# Thermocouple.net
KiCad netlist of a schematic drawn in Altium Designer
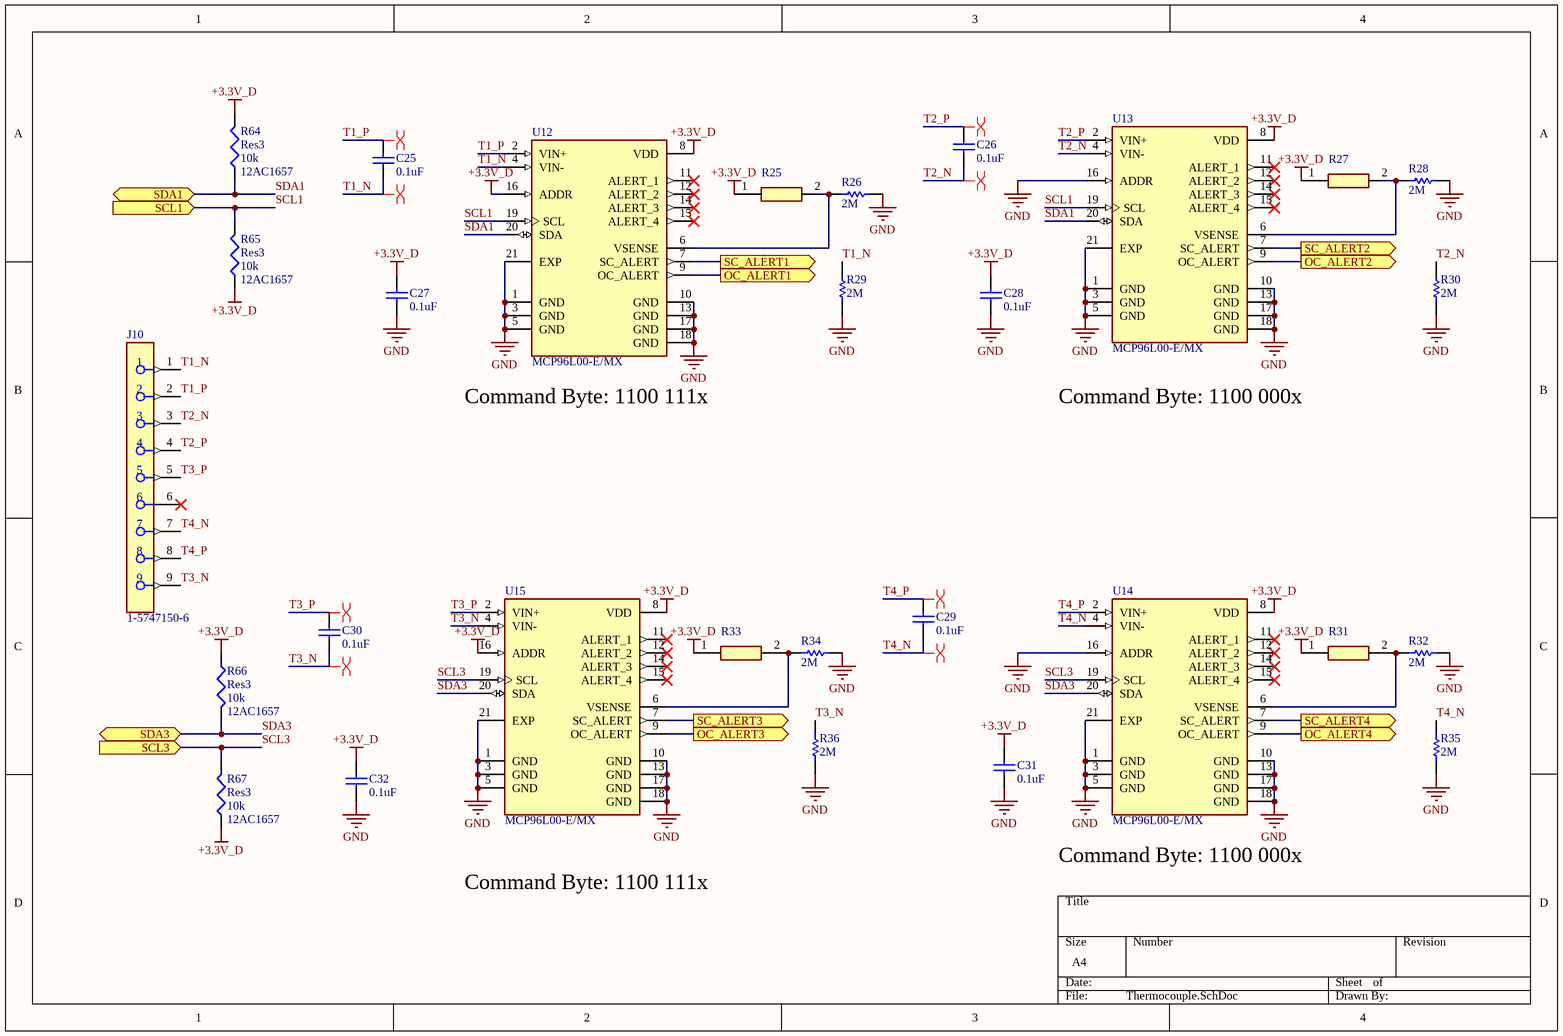
[diagram p0: Thermocouple.SchDoc]

(export (version "E")
  (design (tool "Eeschema 10.0.6"))
  (components
    (comp (ref "C25")
      (value "0.1uF")
      (footprint "CAPC1608X90X35NL15T15")
      (fields
        (field (name "PART NUMBER") "0603YC104JAT2A")
        (field (name "MANUFACTURER") "AVX Interconnect / Elco")
      )
      (libsource (lib "Altium Content Vault") (part "CAP"))
    )
    (comp (ref "C26")
      (value "0.1uF")
      (footprint "CAPC1608X90X35NL15T15")
      (fields
        (field (name "PART NUMBER") "0603YC104JAT2A")
        (field (name "MANUFACTURER") "AVX Interconnect / Elco")
      )
      (libsource (lib "Altium Content Vault") (part "CAP"))
    )
    (comp (ref "C27")
      (value "0.1uF")
      (footprint "CAPC1608X90X35NL15T15")
      (fields
        (field (name "PART NUMBER") "0603YC104JAT2A")
        (field (name "MANUFACTURER") "AVX Interconnect / Elco")
      )
      (libsource (lib "Altium Content Vault") (part "CAP"))
    )
    (comp (ref "C28")
      (value "0.1uF")
      (footprint "CAPC1608X90X35NL15T15")
      (fields
        (field (name "PART NUMBER") "0603YC104JAT2A")
        (field (name "MANUFACTURER") "AVX Interconnect / Elco")
      )
      (libsource (lib "Altium Content Vault") (part "CAP"))
    )
    (comp (ref "C29")
      (value "0.1uF")
      (footprint "CAPC1608X90X35NL15T15")
      (fields
        (field (name "PART NUMBER") "0603YC104JAT2A")
        (field (name "MANUFACTURER") "AVX Interconnect / Elco")
      )
      (libsource (lib "Altium Content Vault") (part "CAP"))
    )
    (comp (ref "C30")
      (value "0.1uF")
      (footprint "CAPC1608X90X35NL15T15")
      (fields
        (field (name "PART NUMBER") "0603YC104JAT2A")
        (field (name "MANUFACTURER") "AVX Interconnect / Elco")
      )
      (libsource (lib "Altium Content Vault") (part "CAP"))
    )
    (comp (ref "C31")
      (value "0.1uF")
      (footprint "CAPC1608X90X35NL15T15")
      (fields
        (field (name "PART NUMBER") "0603YC104JAT2A")
        (field (name "MANUFACTURER") "AVX Interconnect / Elco")
      )
      (libsource (lib "Altium Content Vault") (part "CAP"))
    )
    (comp (ref "C32")
      (value "0.1uF")
      (footprint "CAPC1608X90X35NL15T15")
      (fields
        (field (name "PART NUMBER") "0603YC104JAT2A")
        (field (name "MANUFACTURER") "AVX Interconnect / Elco")
      )
      (libsource (lib "Altium Content Vault") (part "CAP"))
    )
    (comp (ref "J10")
      (value "1-5747150-6")
      (footprint "FP-1-5747150-6-MFG")
      (description "CONN D-SUB RCPT 9POS VERT SOLDER")
      (fields
        (field (name "OCTOPART") "https://octopart.com/1-5747150-6-te+connectivity-39500344")
        (field (name "MANUFACTURER") "TE Connectivity")
      )
      (libsource (lib "Altium Content Vault") (part "deee9d0d87fff07c08bdfa5b86cd5a5"))
    )
    (comp (ref "R25")
      (value "ERJ-U02F1004X")
      (footprint "SamacSys:ERJS02_U02_(0402)")
      (description "Resistor")
      (libsource (lib "*") (part "ERJ-U02F1004X"))
    )
    (comp (ref "R26")
      (value "ERJ-2GEJ205X")
      (footprint "RESC1005X40X25LL05T05")
      (fields (field (name "MANUFACTURER") "Panasonic") (field (name "RESISTANCE") "2M"))
      (libsource (lib "Altium Content Vault") (part "RES"))
    )
    (comp (ref "R27")
      (value "ERJ-U02F1004X")
      (footprint "SamacSys:ERJS02_U02_(0402)")
      (description "Resistor")
      (libsource (lib "*") (part "ERJ-U02F1004X"))
    )
    (comp (ref "R28")
      (value "ERJ-2GEJ205X")
      (footprint "RESC1005X40X25LL05T05")
      (fields (field (name "MANUFACTURER") "Panasonic") (field (name "RESISTANCE") "2M"))
      (libsource (lib "Altium Content Vault") (part "RES"))
    )
    (comp (ref "R29")
      (value "ERJ-2GEJ205X")
      (footprint "RESC1005X40X25LL05T05")
      (fields (field (name "MANUFACTURER") "Panasonic") (field (name "RESISTANCE") "2M"))
      (libsource (lib "Altium Content Vault") (part "RES"))
    )
    (comp (ref "R30")
      (value "ERJ-2GEJ205X")
      (footprint "RESC1005X40X25LL05T05")
      (fields (field (name "MANUFACTURER") "Panasonic") (field (name "RESISTANCE") "2M"))
      (libsource (lib "Altium Content Vault") (part "RES"))
    )
    (comp (ref "R31")
      (value "ERJ-U02F1004X")
      (footprint "SamacSys:ERJS02_U02_(0402)")
      (description "Resistor")
      (libsource (lib "*") (part "ERJ-U02F1004X"))
    )
    (comp (ref "R32")
      (value "ERJ-2GEJ205X")
      (footprint "RESC1005X40X25LL05T05")
      (fields (field (name "MANUFACTURER") "Panasonic") (field (name "RESISTANCE") "2M"))
      (libsource (lib "Altium Content Vault") (part "RES"))
    )
    (comp (ref "R33")
      (value "ERJ-U02F1004X")
      (footprint "SamacSys:ERJS02_U02_(0402)")
      (description "Resistor")
      (libsource (lib "*") (part "ERJ-U02F1004X"))
    )
    (comp (ref "R34")
      (value "ERJ-2GEJ205X")
      (footprint "RESC1005X40X25LL05T05")
      (fields (field (name "MANUFACTURER") "Panasonic") (field (name "RESISTANCE") "2M"))
      (libsource (lib "Altium Content Vault") (part "RES"))
    )
    (comp (ref "R35")
      (value "ERJ-2GEJ205X")
      (footprint "RESC1005X40X25LL05T05")
      (fields (field (name "MANUFACTURER") "Panasonic") (field (name "RESISTANCE") "2M"))
      (libsource (lib "Altium Content Vault") (part "RES"))
    )
    (comp (ref "R36")
      (value "ERJ-2GEJ205X")
      (footprint "RESC1005X40X25LL05T05")
      (fields (field (name "MANUFACTURER") "Panasonic") (field (name "RESISTANCE") "2M"))
      (libsource (lib "Altium Content Vault") (part "RES"))
    )
    (comp (ref "R64")
      (value "Res3")
      (footprint "6-0805_L")
      (description "VISHAY BC COMPONENTS   MCT06030C1002FP500   RESISTOR, 0603, 10KOHM, 100mW, 1PER")
      (fields
        (field (name "ALTIUM_VALUE") "10k")
        (field (name "SUPPLIER PART NUMBER 1") "12AC1657")
        (field (name "MANUFACTURER") "Vishay")
        (field (name "MANUFACTURER PART NUMBER") "MCT06030C1002FP500")
        (field (name "PUBLISHER") "Altium Limited")
      )
      (libsource (lib "Miscellaneous Devices") (part "Res3"))
    )
    (comp (ref "R65")
      (value "Res3")
      (footprint "6-0805_L")
      (description "VISHAY BC COMPONENTS   MCT06030C1002FP500   RESISTOR, 0603, 10KOHM, 100mW, 1PER")
      (fields
        (field (name "ALTIUM_VALUE") "10k")
        (field (name "SUPPLIER PART NUMBER 1") "12AC1657")
        (field (name "MANUFACTURER") "Vishay")
        (field (name "MANUFACTURER PART NUMBER") "MCT06030C1002FP500")
        (field (name "PUBLISHER") "Altium Limited")
      )
      (libsource (lib "Miscellaneous Devices") (part "Res3"))
    )
    (comp (ref "R66")
      (value "Res3")
      (footprint "6-0805_L")
      (description "VISHAY BC COMPONENTS   MCT06030C1002FP500   RESISTOR, 0603, 10KOHM, 100mW, 1PER")
      (fields
        (field (name "ALTIUM_VALUE") "10k")
        (field (name "SUPPLIER PART NUMBER 1") "12AC1657")
        (field (name "MANUFACTURER") "Vishay")
        (field (name "MANUFACTURER PART NUMBER") "MCT06030C1002FP500")
        (field (name "PUBLISHER") "Altium Limited")
      )
      (libsource (lib "Miscellaneous Devices") (part "Res3"))
    )
    (comp (ref "R67")
      (value "Res3")
      (footprint "6-0805_L")
      (description "VISHAY BC COMPONENTS   MCT06030C1002FP500   RESISTOR, 0603, 10KOHM, 100mW, 1PER")
      (fields
        (field (name "ALTIUM_VALUE") "10k")
        (field (name "SUPPLIER PART NUMBER 1") "12AC1657")
        (field (name "MANUFACTURER") "Vishay")
        (field (name "MANUFACTURER PART NUMBER") "MCT06030C1002FP500")
        (field (name "PUBLISHER") "Altium Limited")
      )
      (libsource (lib "Miscellaneous Devices") (part "Res3"))
    )
    (comp (ref "U12")
      (value "MCP96L00-E/MX")
      (footprint "WB-AV-4510-DAQ:QFN65P500X500X100-21N_MCP9600-E/MX")
      (description "IC THERMOCOUPLE TO I2C 20MQFN")
      (fields (field (name "MF") "Microchip"))
      (libsource (lib "WB-AV-4510-DAQ") (part "MCP96001-E/MX"))
    )
    (comp (ref "U13")
      (value "MCP96L00-E/MX")
      (footprint "WB-AV-4510-DAQ:QFN65P500X500X100-21N_MCP9600-E/MX")
      (description "IC THERMOCOUPLE TO I2C 20MQFN")
      (fields (field (name "MF") "Microchip"))
      (libsource (lib "WB-AV-4510-DAQ") (part "MCP96001-E/MX"))
    )
    (comp (ref "U14")
      (value "MCP96L00-E/MX")
      (footprint "WB-AV-4510-DAQ:QFN65P500X500X100-21N_MCP9600-E/MX")
      (description "IC THERMOCOUPLE TO I2C 20MQFN")
      (fields (field (name "MF") "Microchip"))
      (libsource (lib "WB-AV-4510-DAQ") (part "MCP96001-E/MX"))
    )
    (comp (ref "U15")
      (value "MCP96L00-E/MX")
      (footprint "WB-AV-4510-DAQ:QFN65P500X500X100-21N_MCP9600-E/MX")
      (description "IC THERMOCOUPLE TO I2C 20MQFN")
      (fields (field (name "MF") "Microchip"))
      (libsource (lib "WB-AV-4510-DAQ") (part "MCP96001-E/MX"))
    )
  )
  (nets
    (net (code "1") (name "+3.3V_D") (class "Default")
      (node (ref "C27") (pin "2") (pinfunction "2_2") (pintype "passive"))
      (node (ref "C28") (pin "2") (pinfunction "2_2") (pintype "passive"))
      (node (ref "C31") (pin "2") (pinfunction "2_2") (pintype "passive"))
      (node (ref "C32") (pin "2") (pinfunction "2_2") (pintype "passive"))
      (node (ref "R25") (pin "1") (pinfunction "1_1") (pintype "passive"))
      (node (ref "R27") (pin "1") (pinfunction "1_1") (pintype "passive"))
      (node (ref "R31") (pin "1") (pinfunction "1_1") (pintype "passive"))
      (node (ref "R33") (pin "1") (pinfunction "1_1") (pintype "passive"))
      (node (ref "R64") (pin "2") (pinfunction "2_2") (pintype "passive"))
      (node (ref "R65") (pin "1") (pinfunction "1_1") (pintype "passive"))
      (node (ref "R66") (pin "1") (pinfunction "1_1") (pintype "passive"))
      (node (ref "R67") (pin "1") (pinfunction "1_1") (pintype "passive"))
      (node (ref "U12") (pin "16") (pinfunction "ADDR_16") (pintype "input"))
      (node (ref "U12") (pin "8") (pinfunction "VDD_8") (pintype "power_in"))
      (node (ref "U13") (pin "8") (pinfunction "VDD_8") (pintype "power_in"))
      (node (ref "U14") (pin "8") (pinfunction "VDD_8") (pintype "power_in"))
      (node (ref "U15") (pin "16") (pinfunction "ADDR_16") (pintype "input"))
      (node (ref "U15") (pin "8") (pinfunction "VDD_8") (pintype "power_in"))
    )
    (net (code "2") (name "/OC_ALERT1") (class "Default")
      (node (ref "U12") (pin "9") (pinfunction "OC_ALERT_9") (pintype "output"))
    )
    (net (code "3") (name "/OC_ALERT2") (class "Default")
      (node (ref "U13") (pin "9") (pinfunction "OC_ALERT_9") (pintype "output"))
    )
    (net (code "4") (name "/OC_ALERT3") (class "Default")
      (node (ref "U15") (pin "9") (pinfunction "OC_ALERT_9") (pintype "output"))
    )
    (net (code "5") (name "/OC_ALERT4") (class "Default")
      (node (ref "U14") (pin "9") (pinfunction "OC_ALERT_9") (pintype "output"))
    )
    (net (code "6") (name "/SCL1") (class "Default")
      (node (ref "R65") (pin "2") (pinfunction "2_2") (pintype "passive"))
      (node (ref "U12") (pin "19") (pinfunction "SCL_19") (pintype "input"))
      (node (ref "U13") (pin "19") (pinfunction "SCL_19") (pintype "input"))
    )
    (net (code "7") (name "/SCL3") (class "Default")
      (node (ref "R67") (pin "2") (pinfunction "2_2") (pintype "passive"))
      (node (ref "U14") (pin "19") (pinfunction "SCL_19") (pintype "input"))
      (node (ref "U15") (pin "19") (pinfunction "SCL_19") (pintype "input"))
    )
    (net (code "8") (name "/SC_ALERT1") (class "Default")
      (node (ref "U12") (pin "7") (pinfunction "SC_ALERT_7") (pintype "output"))
    )
    (net (code "9") (name "/SC_ALERT2") (class "Default")
      (node (ref "U13") (pin "7") (pinfunction "SC_ALERT_7") (pintype "output"))
    )
    (net (code "10") (name "/SC_ALERT3") (class "Default")
      (node (ref "U15") (pin "7") (pinfunction "SC_ALERT_7") (pintype "output"))
    )
    (net (code "11") (name "/SC_ALERT4") (class "Default")
      (node (ref "U14") (pin "7") (pinfunction "SC_ALERT_7") (pintype "output"))
    )
    (net (code "12") (name "/SDA1") (class "Default")
      (node (ref "R64") (pin "1") (pinfunction "1_1") (pintype "passive"))
      (node (ref "U12") (pin "20") (pinfunction "SDA_20") (pintype "bidirectional"))
      (node (ref "U13") (pin "20") (pinfunction "SDA_20") (pintype "bidirectional"))
    )
    (net (code "13") (name "/SDA3") (class "Default")
      (node (ref "R66") (pin "2") (pinfunction "2_2") (pintype "passive"))
      (node (ref "U14") (pin "20") (pinfunction "SDA_20") (pintype "bidirectional"))
      (node (ref "U15") (pin "20") (pinfunction "SDA_20") (pintype "bidirectional"))
    )
    (net (code "14") (name "/T1_N") (class "Default")
      (node (ref "C25") (pin "1") (pinfunction "1_1") (pintype "passive"))
      (node (ref "J10") (pin "1") (pinfunction "1_1") (pintype "output"))
      (node (ref "R29") (pin "2") (pinfunction "2_2") (pintype "passive"))
      (node (ref "U12") (pin "4") (pinfunction "VIN-_4") (pintype "input"))
    )
    (net (code "15") (name "/T1_P") (class "Default")
      (node (ref "C25") (pin "2") (pinfunction "2_2") (pintype "passive"))
      (node (ref "J10") (pin "2") (pinfunction "2_2") (pintype "output"))
      (node (ref "U12") (pin "2") (pinfunction "VIN+_2") (pintype "input"))
    )
    (net (code "16") (name "/T2_N") (class "Default")
      (node (ref "C26") (pin "1") (pinfunction "1_1") (pintype "passive"))
      (node (ref "J10") (pin "3") (pinfunction "3_3") (pintype "output"))
      (node (ref "R30") (pin "2") (pinfunction "2_2") (pintype "passive"))
      (node (ref "U13") (pin "4") (pinfunction "VIN-_4") (pintype "input"))
    )
    (net (code "17") (name "/T2_P") (class "Default")
      (node (ref "C26") (pin "2") (pinfunction "2_2") (pintype "passive"))
      (node (ref "J10") (pin "4") (pinfunction "4_4") (pintype "output"))
      (node (ref "U13") (pin "2") (pinfunction "VIN+_2") (pintype "input"))
    )
    (net (code "18") (name "/T3_N") (class "Default")
      (node (ref "C30") (pin "1") (pinfunction "1_1") (pintype "passive"))
      (node (ref "J10") (pin "9") (pinfunction "9_9") (pintype "output"))
      (node (ref "R36") (pin "2") (pinfunction "2_2") (pintype "passive"))
      (node (ref "U15") (pin "4") (pinfunction "VIN-_4") (pintype "input"))
    )
    (net (code "19") (name "/T3_P") (class "Default")
      (node (ref "C30") (pin "2") (pinfunction "2_2") (pintype "passive"))
      (node (ref "J10") (pin "5") (pinfunction "5_5") (pintype "output"))
      (node (ref "U15") (pin "2") (pinfunction "VIN+_2") (pintype "input"))
    )
    (net (code "20") (name "/T4_N") (class "Default")
      (node (ref "C29") (pin "1") (pinfunction "1_1") (pintype "passive"))
      (node (ref "J10") (pin "7") (pinfunction "7_7") (pintype "output"))
      (node (ref "R35") (pin "2") (pinfunction "2_2") (pintype "passive"))
      (node (ref "U14") (pin "4") (pinfunction "VIN-_4") (pintype "input"))
    )
    (net (code "21") (name "/T4_P") (class "Default")
      (node (ref "C29") (pin "2") (pinfunction "2_2") (pintype "passive"))
      (node (ref "J10") (pin "8") (pinfunction "8_8") (pintype "output"))
      (node (ref "U14") (pin "2") (pinfunction "VIN+_2") (pintype "input"))
    )
    (net (code "22") (name "GND") (class "Default")
      (node (ref "C27") (pin "1") (pinfunction "1_1") (pintype "passive"))
      (node (ref "C28") (pin "1") (pinfunction "1_1") (pintype "passive"))
      (node (ref "C31") (pin "1") (pinfunction "1_1") (pintype "passive"))
      (node (ref "C32") (pin "1") (pinfunction "1_1") (pintype "passive"))
      (node (ref "R26") (pin "2") (pinfunction "2_2") (pintype "passive"))
      (node (ref "R28") (pin "2") (pinfunction "2_2") (pintype "passive"))
      (node (ref "R29") (pin "1") (pinfunction "1_1") (pintype "passive"))
      (node (ref "R30") (pin "1") (pinfunction "1_1") (pintype "passive"))
      (node (ref "R32") (pin "2") (pinfunction "2_2") (pintype "passive"))
      (node (ref "R34") (pin "2") (pinfunction "2_2") (pintype "passive"))
      (node (ref "R35") (pin "1") (pinfunction "1_1") (pintype "passive"))
      (node (ref "R36") (pin "1") (pinfunction "1_1") (pintype "passive"))
      (node (ref "U12") (pin "1") (pinfunction "GND_1") (pintype "power_in"))
      (node (ref "U12") (pin "10") (pinfunction "GND_10") (pintype "power_in"))
      (node (ref "U12") (pin "13") (pinfunction "GND_13") (pintype "power_in"))
      (node (ref "U12") (pin "17") (pinfunction "GND_17") (pintype "power_in"))
      (node (ref "U12") (pin "18") (pinfunction "GND_18") (pintype "power_in"))
      (node (ref "U12") (pin "21") (pinfunction "EXP_21") (pintype "power_in"))
      (node (ref "U12") (pin "3") (pinfunction "GND_3") (pintype "power_in"))
      (node (ref "U12") (pin "5") (pinfunction "GND_5") (pintype "power_in"))
      (node (ref "U13") (pin "1") (pinfunction "GND_1") (pintype "power_in"))
      (node (ref "U13") (pin "10") (pinfunction "GND_10") (pintype "power_in"))
      (node (ref "U13") (pin "13") (pinfunction "GND_13") (pintype "power_in"))
      (node (ref "U13") (pin "16") (pinfunction "ADDR_16") (pintype "input"))
      (node (ref "U13") (pin "17") (pinfunction "GND_17") (pintype "power_in"))
      (node (ref "U13") (pin "18") (pinfunction "GND_18") (pintype "power_in"))
      (node (ref "U13") (pin "21") (pinfunction "EXP_21") (pintype "power_in"))
      (node (ref "U13") (pin "3") (pinfunction "GND_3") (pintype "power_in"))
      (node (ref "U13") (pin "5") (pinfunction "GND_5") (pintype "power_in"))
      (node (ref "U14") (pin "1") (pinfunction "GND_1") (pintype "power_in"))
      (node (ref "U14") (pin "10") (pinfunction "GND_10") (pintype "power_in"))
      (node (ref "U14") (pin "13") (pinfunction "GND_13") (pintype "power_in"))
      (node (ref "U14") (pin "16") (pinfunction "ADDR_16") (pintype "input"))
      (node (ref "U14") (pin "17") (pinfunction "GND_17") (pintype "power_in"))
      (node (ref "U14") (pin "18") (pinfunction "GND_18") (pintype "power_in"))
      (node (ref "U14") (pin "21") (pinfunction "EXP_21") (pintype "power_in"))
      (node (ref "U14") (pin "3") (pinfunction "GND_3") (pintype "power_in"))
      (node (ref "U14") (pin "5") (pinfunction "GND_5") (pintype "power_in"))
      (node (ref "U15") (pin "1") (pinfunction "GND_1") (pintype "power_in"))
      (node (ref "U15") (pin "10") (pinfunction "GND_10") (pintype "power_in"))
      (node (ref "U15") (pin "13") (pinfunction "GND_13") (pintype "power_in"))
      (node (ref "U15") (pin "17") (pinfunction "GND_17") (pintype "power_in"))
      (node (ref "U15") (pin "18") (pinfunction "GND_18") (pintype "power_in"))
      (node (ref "U15") (pin "21") (pinfunction "EXP_21") (pintype "power_in"))
      (node (ref "U15") (pin "3") (pinfunction "GND_3") (pintype "power_in"))
      (node (ref "U15") (pin "5") (pinfunction "GND_5") (pintype "power_in"))
    )
    (net (code "23") (name "Net-(U12-VSENSE)") (class "Default")
      (node (ref "R25") (pin "2") (pinfunction "2_2") (pintype "passive"))
      (node (ref "R26") (pin "1") (pinfunction "1_1") (pintype "passive"))
      (node (ref "U12") (pin "6") (pinfunction "VSENSE_6") (pintype "power_in"))
    )
    (net (code "24") (name "Net-(U13-VSENSE)") (class "Default")
      (node (ref "R27") (pin "2") (pinfunction "2_2") (pintype "passive"))
      (node (ref "R28") (pin "1") (pinfunction "1_1") (pintype "passive"))
      (node (ref "U13") (pin "6") (pinfunction "VSENSE_6") (pintype "power_in"))
    )
    (net (code "25") (name "Net-(U14-VSENSE)") (class "Default")
      (node (ref "R31") (pin "2") (pinfunction "2_2") (pintype "passive"))
      (node (ref "R32") (pin "1") (pinfunction "1_1") (pintype "passive"))
      (node (ref "U14") (pin "6") (pinfunction "VSENSE_6") (pintype "power_in"))
    )
    (net (code "26") (name "Net-(U15-VSENSE)") (class "Default")
      (node (ref "R33") (pin "2") (pinfunction "2_2") (pintype "passive"))
      (node (ref "R34") (pin "1") (pinfunction "1_1") (pintype "passive"))
      (node (ref "U15") (pin "6") (pinfunction "VSENSE_6") (pintype "power_in"))
    )
    (net (code "27") (name "unconnected-(J10-Pad6)") (class "Default")
      (node (ref "J10") (pin "6") (pinfunction "6_6") (pintype "passive+no_connect"))
    )
    (net (code "28") (name "unconnected-(U12-ALERT_1-Pad11)") (class "Default")
      (node (ref "U12") (pin "11") (pinfunction "ALERT_1_11") (pintype "output+no_connect"))
    )
    (net (code "29") (name "unconnected-(U12-ALERT_2-Pad12)") (class "Default")
      (node (ref "U12") (pin "12") (pinfunction "ALERT_2_12") (pintype "output+no_connect"))
    )
    (net (code "30") (name "unconnected-(U12-ALERT_3-Pad14)") (class "Default")
      (node (ref "U12") (pin "14") (pinfunction "ALERT_3_14") (pintype "output+no_connect"))
    )
    (net (code "31") (name "unconnected-(U12-ALERT_4-Pad15)") (class "Default")
      (node (ref "U12") (pin "15") (pinfunction "ALERT_4_15") (pintype "output+no_connect"))
    )
    (net (code "32") (name "unconnected-(U13-ALERT_1-Pad11)") (class "Default")
      (node (ref "U13") (pin "11") (pinfunction "ALERT_1_11") (pintype "output+no_connect"))
    )
    (net (code "33") (name "unconnected-(U13-ALERT_2-Pad12)") (class "Default")
      (node (ref "U13") (pin "12") (pinfunction "ALERT_2_12") (pintype "output+no_connect"))
    )
    (net (code "34") (name "unconnected-(U13-ALERT_3-Pad14)") (class "Default")
      (node (ref "U13") (pin "14") (pinfunction "ALERT_3_14") (pintype "output+no_connect"))
    )
    (net (code "35") (name "unconnected-(U13-ALERT_4-Pad15)") (class "Default")
      (node (ref "U13") (pin "15") (pinfunction "ALERT_4_15") (pintype "output+no_connect"))
    )
    (net (code "36") (name "unconnected-(U14-ALERT_1-Pad11)") (class "Default")
      (node (ref "U14") (pin "11") (pinfunction "ALERT_1_11") (pintype "output+no_connect"))
    )
    (net (code "37") (name "unconnected-(U14-ALERT_2-Pad12)") (class "Default")
      (node (ref "U14") (pin "12") (pinfunction "ALERT_2_12") (pintype "output+no_connect"))
    )
    (net (code "38") (name "unconnected-(U14-ALERT_3-Pad14)") (class "Default")
      (node (ref "U14") (pin "14") (pinfunction "ALERT_3_14") (pintype "output+no_connect"))
    )
    (net (code "39") (name "unconnected-(U14-ALERT_4-Pad15)") (class "Default")
      (node (ref "U14") (pin "15") (pinfunction "ALERT_4_15") (pintype "output+no_connect"))
    )
    (net (code "40") (name "unconnected-(U15-ALERT_1-Pad11)") (class "Default")
      (node (ref "U15") (pin "11") (pinfunction "ALERT_1_11") (pintype "output+no_connect"))
    )
    (net (code "41") (name "unconnected-(U15-ALERT_2-Pad12)") (class "Default")
      (node (ref "U15") (pin "12") (pinfunction "ALERT_2_12") (pintype "output+no_connect"))
    )
    (net (code "42") (name "unconnected-(U15-ALERT_3-Pad14)") (class "Default")
      (node (ref "U15") (pin "14") (pinfunction "ALERT_3_14") (pintype "output+no_connect"))
    )
    (net (code "43") (name "unconnected-(U15-ALERT_4-Pad15)") (class "Default")
      (node (ref "U15") (pin "15") (pinfunction "ALERT_4_15") (pintype "output+no_connect"))
    )
  )
)
